# charger.net
KiCad netlist of a schematic drawn in Altium Designer
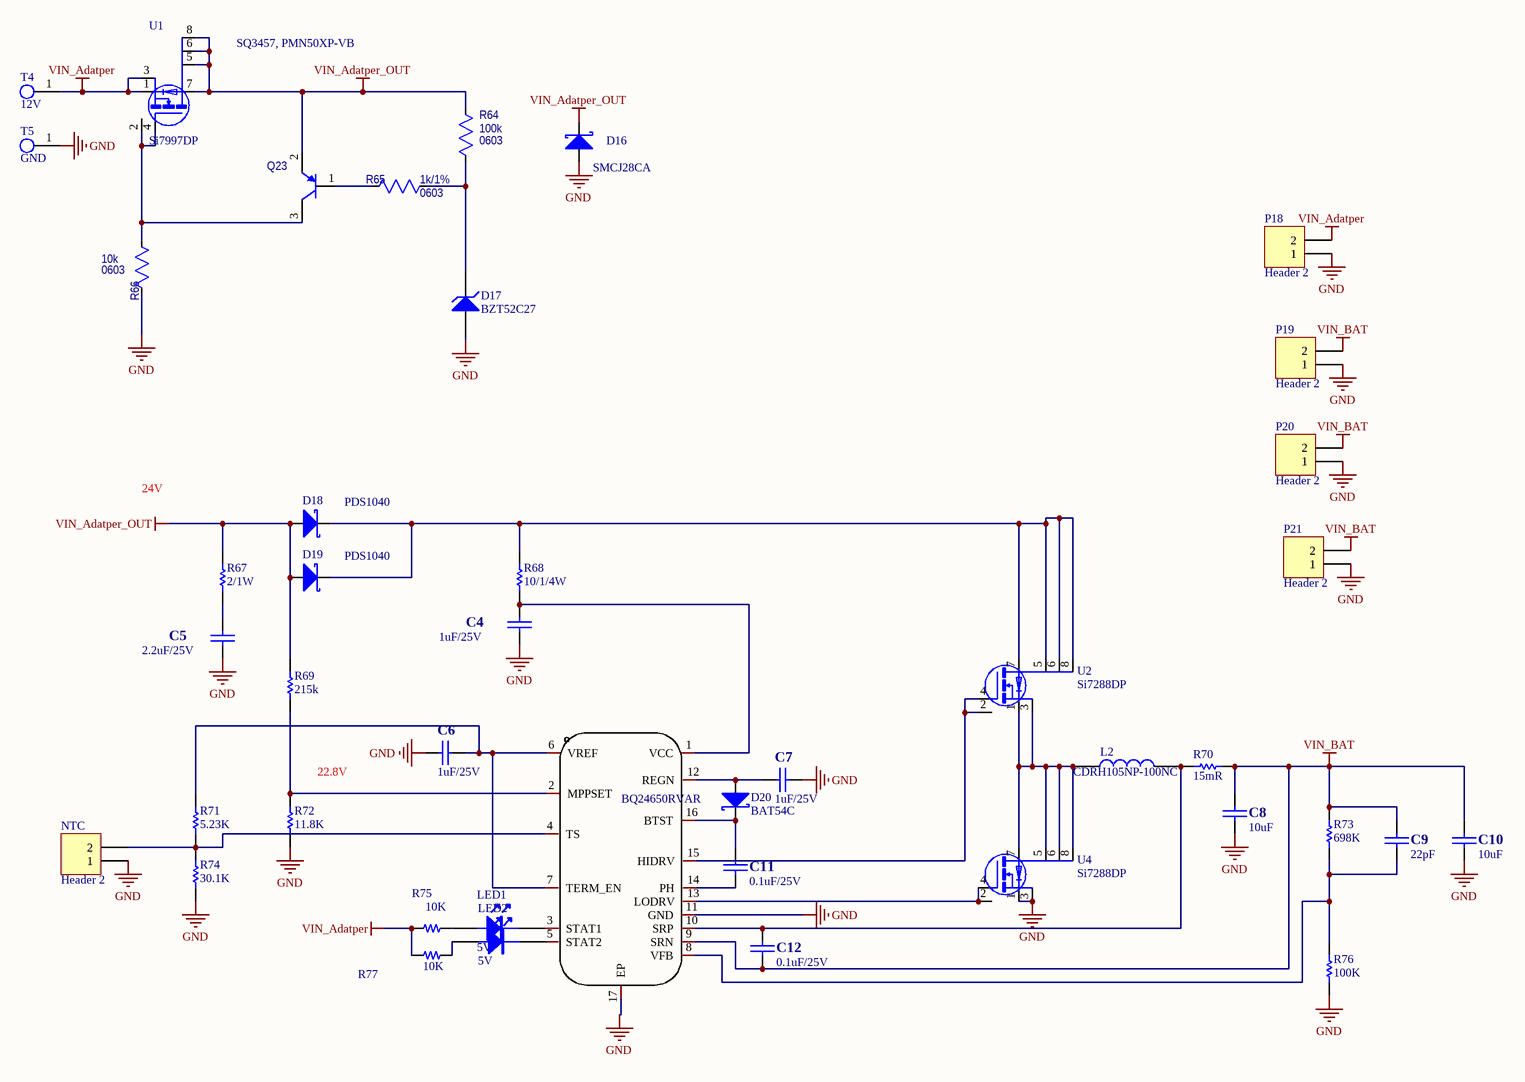
[diagram p0: charger.SchDoc]

(export (version "E")
  (design (tool "Eeschema 10.0.6"))
  (components
    (comp (ref "C4")
      (value "1uF/25V")
      (footprint "0805C")
      (description "Capacitor")
      (libsource (lib "*") (part "CAP"))
    )
    (comp (ref "C5")
      (value "2.2uF/25V")
      (footprint "1210C")
      (description "Capacitor")
      (libsource (lib "*") (part "CAP"))
    )
    (comp (ref "C6")
      (value "1uF/25V")
      (footprint "0603C")
      (description "Capacitor")
      (libsource (lib "*") (part "CAP"))
    )
    (comp (ref "C7")
      (value "1uF/25V")
      (footprint "0603C")
      (description "Capacitor")
      (libsource (lib "*") (part "CAP"))
    )
    (comp (ref "C8")
      (value "10uF")
      (footprint "0603C")
      (description "Capacitor")
      (libsource (lib "*") (part "CAP"))
    )
    (comp (ref "C9")
      (value "22pF")
      (footprint "0603C")
      (description "Capacitor")
      (libsource (lib "*") (part "CAP"))
    )
    (comp (ref "C10")
      (value "10uF")
      (footprint "0603C")
      (description "Capacitor")
      (libsource (lib "*") (part "CAP"))
    )
    (comp (ref "C11")
      (value "0.1uF/25V")
      (footprint "0603C")
      (description "Capacitor")
      (libsource (lib "*") (part "CAP"))
    )
    (comp (ref "C12")
      (value "0.1uF/25V")
      (footprint "0603C")
      (description "Capacitor")
      (libsource (lib "*") (part "CAP"))
    )
    (comp (ref "D16")
      (value "SMCJ28CA")
      (footprint "SMC")
      (description "Schottky Diode")
      (libsource (lib "*") (part "DIODE S"))
    )
    (comp (ref "D17")
      (value "BZT52C27")
      (footprint "sod123")
      (libsource (lib "Bogen") (part "BZT52C12S-7-F"))
    )
    (comp (ref "D18")
      (value "PDS1040")
      (footprint "SMA")
      (description "Schottky Diode")
      (libsource (lib "*") (part "DIODE S"))
    )
    (comp (ref "D19")
      (value "PDS1040")
      (footprint "SMA")
      (description "Schottky Diode")
      (libsource (lib "*") (part "DIODE S"))
    )
    (comp (ref "D20") (value "BAT54C") (description "Schottky Diode") (libsource (lib "*") (part "DIODE S")))
    (comp (ref "L2") (value "CDRH105NP-100NC") (footprint "CDRH105") (libsource (lib "*") (part "INDUCTOR")))
    (comp (ref "LED1") (value "5V") (footprint "0603LED") (libsource (lib "*") (part "LED")))
    (comp (ref "LED2") (value "5V") (footprint "0603LED") (libsource (lib "*") (part "LED")))
    (comp (ref "NTC")
      (value "Header 2")
      (footprint "HDR1X2")
      (description "Header, 2-Pin")
      (fields (field (name "PUBLISHER") "Altium Limited"))
      (libsource (lib "Miscellaneous Connectors") (part "Header 2"))
    )
    (comp (ref "P18")
      (value "Header 2")
      (footprint "HDR1X2")
      (description "Header, 2-Pin")
      (fields (field (name "PUBLISHER") "Altium Limited"))
      (libsource (lib "Miscellaneous Connectors") (part "Header 2"))
    )
    (comp (ref "P19")
      (value "Header 2")
      (footprint "HDR1X2")
      (description "Header, 2-Pin")
      (fields (field (name "PUBLISHER") "Altium Limited"))
      (libsource (lib "Miscellaneous Connectors") (part "Header 2"))
    )
    (comp (ref "P20")
      (value "Header 2")
      (footprint "HDR1X2")
      (description "Header, 2-Pin")
      (fields (field (name "PUBLISHER") "Altium Limited"))
      (libsource (lib "Miscellaneous Connectors") (part "Header 2"))
    )
    (comp (ref "P21")
      (value "Header 2")
      (footprint "HDR1X2")
      (description "Header, 2-Pin")
      (fields (field (name "PUBLISHER") "Altium Limited"))
      (libsource (lib "Miscellaneous Connectors") (part "Header 2"))
    )
    (comp (ref "Q23")
      (value "MMBT4403-7-F")
      (footprint "SOT-23_3N_95P_240x300x100")
      (libsource (lib "Karl") (part "OEM_Diodes_MMBT4403"))
    )
    (comp (ref "R64")
      (value "100k")
      (footprint "RESC1608X055N_0603")
      (fields
        (field (name "PARTNUMBER") "RC0603FR-0716K9L")
        (field (name "TOLERANCE") "tol")
        (field (name "PACKAGE") "0603")
        (field (name "Comment") "Resistor_0603")
      )
      (libsource (lib "Karl") (part "Resistor_0603"))
    )
    (comp (ref "R65")
      (value "1k/1%")
      (footprint "RESC1608X055N_0603")
      (fields
        (field (name "PARTNUMBER") "RC0603FR-071KL")
        (field (name "TOLERANCE") "tol")
        (field (name "PACKAGE") "0603")
        (field (name "Comment") "Resistor_0603")
      )
      (libsource (lib "Karl") (part "Resistor_0603"))
    )
    (comp (ref "R66")
      (value "10k")
      (footprint "RESC1608X055N_0603")
      (fields
        (field (name "PARTNUMBER") "RC0603FR-071KL")
        (field (name "TOLERANCE") "tol")
        (field (name "PACKAGE") "0603")
        (field (name "Comment") "Resistor_0603")
      )
      (libsource (lib "Karl") (part "Resistor_0603"))
    )
    (comp (ref "R67")
      (value "2/1W")
      (footprint "2512R")
      (description "Resistor")
      (fields (field (name "PUBLISHER") "Altium Limited"))
      (libsource (lib "Miscellaneous Devices") (part "Res1"))
    )
    (comp (ref "R68")
      (value "10/1/4W")
      (footprint "1206R")
      (description "Resistor")
      (fields (field (name "PUBLISHER") "Altium Limited"))
      (libsource (lib "Miscellaneous Devices") (part "Res1"))
    )
    (comp (ref "R69")
      (value "215k")
      (footprint "0603R")
      (description "Resistor")
      (fields (field (name "PUBLISHER") "Altium Limited"))
      (libsource (lib "Miscellaneous Devices") (part "Res1"))
    )
    (comp (ref "R70")
      (value "15mR")
      (footprint "2512R")
      (description "Resistor")
      (fields (field (name "PUBLISHER") "Altium Limited"))
      (libsource (lib "Miscellaneous Devices") (part "Res1"))
    )
    (comp (ref "R71")
      (value "5.23K")
      (footprint "0603R")
      (description "Resistor")
      (fields (field (name "PUBLISHER") "Altium Limited"))
      (libsource (lib "Miscellaneous Devices") (part "Res1"))
    )
    (comp (ref "R72")
      (value "11.8K")
      (footprint "0603R")
      (description "Resistor")
      (fields (field (name "PUBLISHER") "Altium Limited"))
      (libsource (lib "Miscellaneous Devices") (part "Res1"))
    )
    (comp (ref "R73")
      (value "698K")
      (footprint "0603R")
      (description "Resistor")
      (fields (field (name "PUBLISHER") "Altium Limited"))
      (libsource (lib "Miscellaneous Devices") (part "Res1"))
    )
    (comp (ref "R74")
      (value "30.1K")
      (footprint "0603R")
      (description "Resistor")
      (fields (field (name "PUBLISHER") "Altium Limited"))
      (libsource (lib "Miscellaneous Devices") (part "Res1"))
    )
    (comp (ref "R75") (value "10K") (footprint "0603R") (libsource (lib "JRJ_1") (part "R")))
    (comp (ref "R76")
      (value "100K")
      (footprint "0603R")
      (description "Resistor")
      (fields (field (name "PUBLISHER") "Altium Limited"))
      (libsource (lib "Miscellaneous Devices") (part "Res1"))
    )
    (comp (ref "R77") (value "10K") (footprint "0603R") (libsource (lib "JRJ_1") (part "R")))
    (comp (ref "T4") (value "12V") (footprint "FIX-4.5") (libsource (lib "Schlib_20110825") (part "TP")))
    (comp (ref "T5") (value "GND") (footprint "FIX-4.5") (libsource (lib "Schlib_20110825") (part "TP")))
    (comp (ref "U1")
      (value "Si7997DP")
      (footprint "SC-70(PowerPAK)")
      (description "Sia430DJ")
      (libsource (lib "Schlib_20110825") (part "Si7997DP"))
    )
    (comp (ref "U2")
      (value "Si7288DP")
      (footprint "SC-70(PowerPAK)")
      (description "Sia430DJ")
      (libsource (lib "Schlib_20110825") (part "Si7997DP"))
    )
    (comp (ref "U4")
      (value "Si7288DP")
      (footprint "SC-70(PowerPAK)")
      (description "Sia430DJ")
      (libsource (lib "Schlib_20110825") (part "Si7997DP"))
    )
    (comp (ref "U5")
      (value "BQ24650RVAR")
      (footprint "VQFN-16_L3.6-W3.6-P0.50-BL-EP")
      (fields (field (name "MANUFACTURER") "TI(德州仪器)"))
      (libsource (lib "Schlib_20110825") (part "BQ24650RVAR"))
    )
  )
  (nets
    (net (code "1") (name "GND") (class "Default")
      (node (ref "C10") (pin "1") (pinfunction "1_1") (pintype "passive"))
      (node (ref "C4") (pin "2") (pinfunction "2_2") (pintype "passive"))
      (node (ref "C5") (pin "2") (pinfunction "2_2") (pintype "passive"))
      (node (ref "C6") (pin "1") (pinfunction "1_1") (pintype "passive"))
      (node (ref "C7") (pin "2") (pinfunction "2_2") (pintype "passive"))
      (node (ref "C8") (pin "1") (pinfunction "1_1") (pintype "passive"))
      (node (ref "D16") (pin "1") (pinfunction "A_1") (pintype "passive"))
      (node (ref "D17") (pin "1") (pinfunction "A_1") (pintype "passive"))
      (node (ref "NTC") (pin "1") (pinfunction "1_1") (pintype "passive"))
      (node (ref "P18") (pin "1") (pinfunction "1_1") (pintype "passive"))
      (node (ref "P19") (pin "1") (pinfunction "1_1") (pintype "passive"))
      (node (ref "P20") (pin "1") (pinfunction "1_1") (pintype "passive"))
      (node (ref "P21") (pin "1") (pinfunction "1_1") (pintype "passive"))
      (node (ref "R66") (pin "2") (pinfunction "2_2") (pintype "passive"))
      (node (ref "R72") (pin "2") (pinfunction "2_2") (pintype "passive"))
      (node (ref "R74") (pin "2") (pinfunction "2_2") (pintype "passive"))
      (node (ref "R76") (pin "2") (pinfunction "2_2") (pintype "passive"))
      (node (ref "T5") (pin "1") (pintype "passive"))
      (node (ref "U4") (pin "1") (pinfunction "S_1") (pintype "passive"))
      (node (ref "U4") (pin "3") (pinfunction "S_3") (pintype "passive"))
      (node (ref "U5") (pin "11") (pinfunction "GND_11") (pintype "passive"))
      (node (ref "U5") (pin "17") (pinfunction "EP_17") (pintype "passive"))
    )
    (net (code "2") (name "Net-(C5-Pad1)") (class "Default")
      (node (ref "C5") (pin "1") (pinfunction "1_1") (pintype "passive"))
      (node (ref "R67") (pin "2") (pinfunction "2_2") (pintype "passive"))
    )
    (net (code "3") (name "Net-(D17-K)") (class "Default")
      (node (ref "D17") (pin "2") (pinfunction "K_2") (pintype "passive"))
      (node (ref "R64") (pin "1") (pinfunction "1_1") (pintype "passive"))
      (node (ref "R65") (pin "1") (pinfunction "1_1") (pintype "passive"))
    )
    (net (code "4") (name "Net-(D18-K)") (class "Default")
      (node (ref "D18") (pin "2") (pinfunction "K_2") (pintype "passive"))
      (node (ref "D19") (pin "2") (pinfunction "K_2") (pintype "passive"))
      (node (ref "R68") (pin "1") (pinfunction "1_1") (pintype "passive"))
      (node (ref "U2") (pin "5") (pinfunction "D_5") (pintype "passive"))
      (node (ref "U2") (pin "6") (pinfunction "D_6") (pintype "passive"))
      (node (ref "U2") (pin "7") (pinfunction "D_7") (pintype "passive"))
      (node (ref "U2") (pin "8") (pinfunction "D_8") (pintype "passive"))
    )
    (net (code "5") (name "Net-(D20-A)") (class "Default")
      (node (ref "C7") (pin "1") (pinfunction "1_1") (pintype "passive"))
      (node (ref "D20") (pin "1") (pinfunction "A_1") (pintype "passive"))
      (node (ref "U5") (pin "12") (pinfunction "REGN_12") (pintype "passive"))
    )
    (net (code "6") (name "Net-(D20-K)") (class "Default")
      (node (ref "C11") (pin "2") (pinfunction "2_2") (pintype "passive"))
      (node (ref "D20") (pin "2") (pinfunction "K_2") (pintype "passive"))
      (node (ref "U5") (pin "16") (pinfunction "BTST_16") (pintype "passive"))
    )
    (net (code "7") (name "Net-(L2-Pad1)") (class "Default")
      (node (ref "L2") (pin "1") (pinfunction "1_1") (pintype "passive"))
      (node (ref "U2") (pin "1") (pinfunction "S_1") (pintype "passive"))
      (node (ref "U2") (pin "3") (pinfunction "S_3") (pintype "passive"))
      (node (ref "U4") (pin "5") (pinfunction "D_5") (pintype "passive"))
      (node (ref "U4") (pin "6") (pinfunction "D_6") (pintype "passive"))
      (node (ref "U4") (pin "7") (pinfunction "D_7") (pintype "passive"))
      (node (ref "U4") (pin "8") (pinfunction "D_8") (pintype "passive"))
    )
    (net (code "8") (name "Net-(LED1-Pad1)") (class "Default")
      (node (ref "LED1") (pin "1") (pinfunction "1_1") (pintype "passive"))
      (node (ref "R75") (pin "1") (pintype "passive"))
    )
    (net (code "9") (name "Net-(LED2-Pad1)") (class "Default")
      (node (ref "LED2") (pin "1") (pinfunction "1_1") (pintype "passive"))
      (node (ref "R77") (pin "1") (pintype "passive"))
    )
    (net (code "10") (name "Net-(Q23-B)") (class "Default")
      (node (ref "Q23") (pin "1") (pinfunction "B_1") (pintype "passive"))
      (node (ref "R65") (pin "2") (pinfunction "2_2") (pintype "passive"))
    )
    (net (code "11") (name "Net-(Q23-C)") (class "Default")
      (node (ref "Q23") (pin "3") (pinfunction "C_3") (pintype "passive"))
      (node (ref "R66") (pin "1") (pinfunction "1_1") (pintype "passive"))
      (node (ref "U1") (pin "2") (pinfunction "G_2") (pintype "passive"))
      (node (ref "U1") (pin "4") (pinfunction "G_4") (pintype "passive"))
    )
    (net (code "12") (name "Net-(U5-HIDRV)") (class "Default")
      (node (ref "U2") (pin "2") (pinfunction "G_2") (pintype "passive"))
      (node (ref "U2") (pin "4") (pinfunction "G_4") (pintype "passive"))
      (node (ref "U5") (pin "15") (pinfunction "HIDRV_15") (pintype "passive"))
    )
    (net (code "13") (name "Net-(U5-LODRV)") (class "Default")
      (node (ref "U4") (pin "2") (pinfunction "G_2") (pintype "passive"))
      (node (ref "U4") (pin "4") (pinfunction "G_4") (pintype "passive"))
      (node (ref "U5") (pin "13") (pinfunction "LODRV_13") (pintype "passive"))
    )
    (net (code "14") (name "Net-(U5-MPPSET)") (class "Default")
      (node (ref "R69") (pin "2") (pinfunction "2_2") (pintype "passive"))
      (node (ref "R72") (pin "1") (pinfunction "1_1") (pintype "passive"))
      (node (ref "U5") (pin "2") (pinfunction "MPPSET_2") (pintype "passive"))
    )
    (net (code "15") (name "Net-(U5-PH)") (class "Default")
      (node (ref "C11") (pin "1") (pinfunction "1_1") (pintype "passive"))
      (node (ref "U5") (pin "14") (pinfunction "PH_14") (pintype "passive"))
    )
    (net (code "16") (name "Net-(U5-SRP)") (class "Default")
      (node (ref "C12") (pin "2") (pinfunction "2_2") (pintype "passive"))
      (node (ref "L2") (pin "2") (pinfunction "2_2") (pintype "passive"))
      (node (ref "R70") (pin "1") (pinfunction "1_1") (pintype "passive"))
      (node (ref "U5") (pin "10") (pinfunction "SRP_10") (pintype "passive"))
    )
    (net (code "17") (name "Net-(U5-STAT1)") (class "Default")
      (node (ref "LED1") (pin "2") (pinfunction "2_2") (pintype "passive"))
      (node (ref "U5") (pin "3") (pinfunction "STAT1_3") (pintype "passive"))
    )
    (net (code "18") (name "Net-(U5-TERM_EN)") (class "Default")
      (node (ref "C6") (pin "2") (pinfunction "2_2") (pintype "passive"))
      (node (ref "R71") (pin "1") (pinfunction "1_1") (pintype "passive"))
      (node (ref "U5") (pin "6") (pinfunction "VREF_6") (pintype "passive"))
      (node (ref "U5") (pin "7") (pinfunction "TERM_EN_7") (pintype "passive"))
    )
    (net (code "19") (name "Net-(U5-TS)") (class "Default")
      (node (ref "NTC") (pin "2") (pinfunction "2_2") (pintype "passive"))
      (node (ref "R71") (pin "2") (pinfunction "2_2") (pintype "passive"))
      (node (ref "R74") (pin "1") (pinfunction "1_1") (pintype "passive"))
      (node (ref "U5") (pin "4") (pinfunction "TS_4") (pintype "passive"))
    )
    (net (code "20") (name "Net-(U5-VCC)") (class "Default")
      (node (ref "C4") (pin "1") (pinfunction "1_1") (pintype "passive"))
      (node (ref "R68") (pin "2") (pinfunction "2_2") (pintype "passive"))
      (node (ref "U5") (pin "1") (pinfunction "VCC_1") (pintype "passive"))
    )
    (net (code "21") (name "Net-(U5-VFB)") (class "Default")
      (node (ref "C9") (pin "1") (pinfunction "1_1") (pintype "passive"))
      (node (ref "R73") (pin "2") (pinfunction "2_2") (pintype "passive"))
      (node (ref "R76") (pin "1") (pinfunction "1_1") (pintype "passive"))
      (node (ref "U5") (pin "8") (pinfunction "VFB_8") (pintype "passive"))
    )
    (net (code "22") (name "VIN_Adatper") (class "Default")
      (node (ref "P18") (pin "2") (pinfunction "2_2") (pintype "passive"))
      (node (ref "R75") (pin "2") (pintype "passive"))
      (node (ref "R77") (pin "2") (pintype "passive"))
      (node (ref "T4") (pin "1") (pintype "passive"))
      (node (ref "U1") (pin "1") (pinfunction "S_1") (pintype "passive"))
      (node (ref "U1") (pin "3") (pinfunction "S_3") (pintype "passive"))
    )
    (net (code "23") (name "VIN_Adatper_OUT") (class "Default")
      (node (ref "D16") (pin "2") (pinfunction "K_2") (pintype "passive"))
      (node (ref "D18") (pin "1") (pinfunction "A_1") (pintype "passive"))
      (node (ref "D19") (pin "1") (pinfunction "A_1") (pintype "passive"))
      (node (ref "Q23") (pin "2") (pinfunction "E_2") (pintype "passive"))
      (node (ref "R64") (pin "2") (pinfunction "2_2") (pintype "passive"))
      (node (ref "R67") (pin "1") (pinfunction "1_1") (pintype "passive"))
      (node (ref "R69") (pin "1") (pinfunction "1_1") (pintype "passive"))
      (node (ref "U1") (pin "5") (pinfunction "D_5") (pintype "passive"))
      (node (ref "U1") (pin "6") (pinfunction "D_6") (pintype "passive"))
      (node (ref "U1") (pin "7") (pinfunction "D_7") (pintype "passive"))
      (node (ref "U1") (pin "8") (pinfunction "D_8") (pintype "passive"))
    )
    (net (code "24") (name "VIN_BAT") (class "Default")
      (node (ref "C10") (pin "2") (pinfunction "2_2") (pintype "passive"))
      (node (ref "C12") (pin "1") (pinfunction "1_1") (pintype "passive"))
      (node (ref "C8") (pin "2") (pinfunction "2_2") (pintype "passive"))
      (node (ref "C9") (pin "2") (pinfunction "2_2") (pintype "passive"))
      (node (ref "P19") (pin "2") (pinfunction "2_2") (pintype "passive"))
      (node (ref "P20") (pin "2") (pinfunction "2_2") (pintype "passive"))
      (node (ref "P21") (pin "2") (pinfunction "2_2") (pintype "passive"))
      (node (ref "R70") (pin "2") (pinfunction "2_2") (pintype "passive"))
      (node (ref "R73") (pin "1") (pinfunction "1_1") (pintype "passive"))
      (node (ref "U5") (pin "9") (pinfunction "SRN_9") (pintype "passive"))
    )
    (net (code "25") (name "unconnected-(LED2-Pad2)") (class "Default")
      (node (ref "LED2") (pin "2") (pinfunction "2_2") (pintype "passive"))
    )
    (net (code "26") (name "unconnected-(U5-STAT2-Pad5)") (class "Default")
      (node (ref "U5") (pin "5") (pinfunction "STAT2_5") (pintype "passive"))
    )
  )
)
